# SPI_MUX.net
KiCad netlist of a schematic drawn in EAGLE
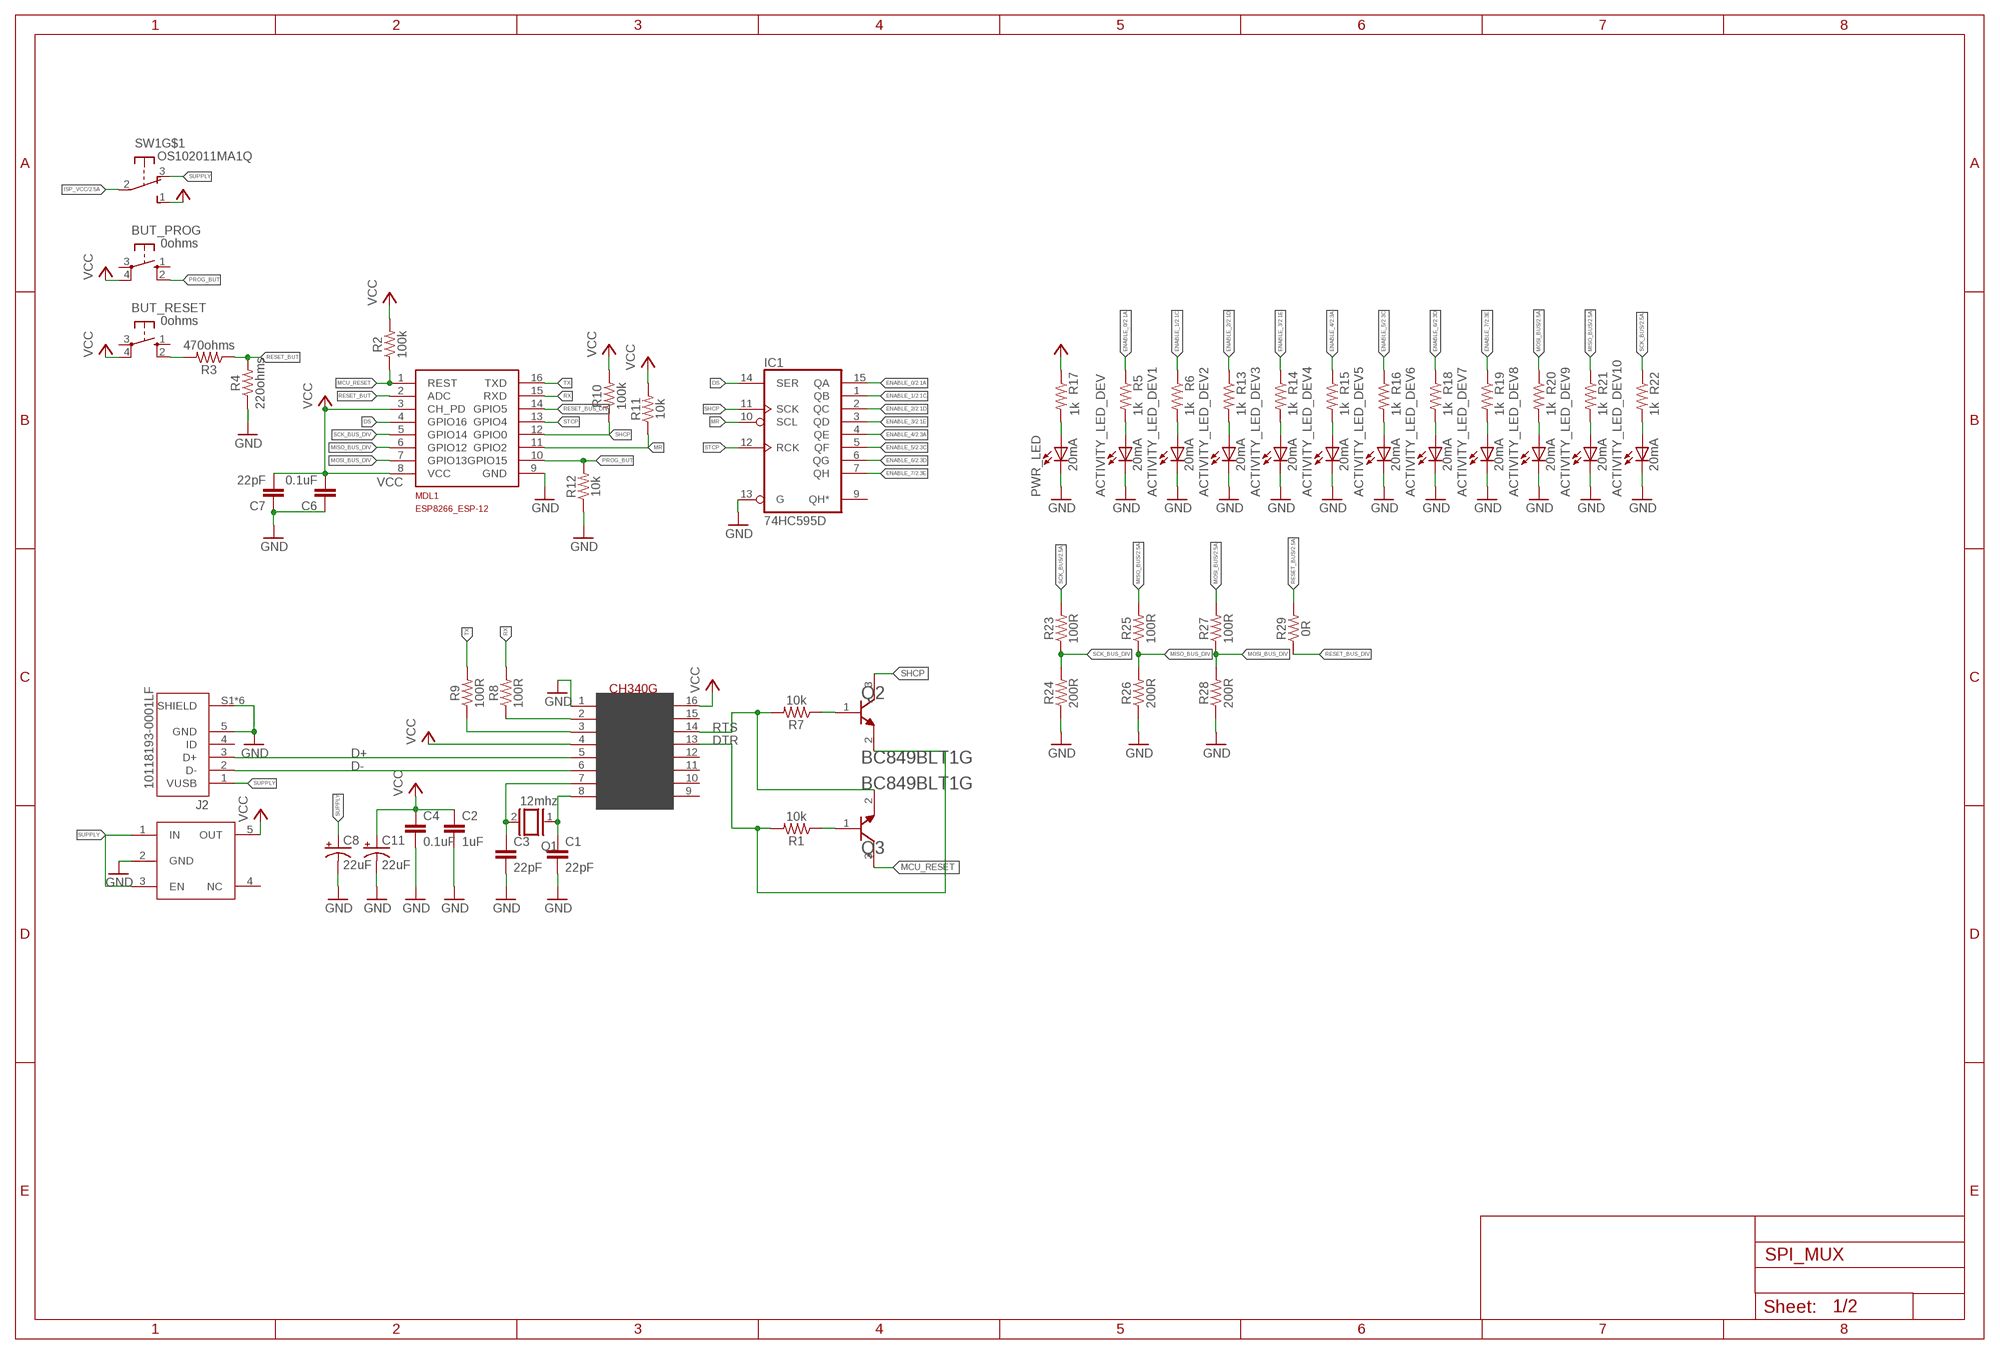
[diagram p0: schematic, sheet 1]
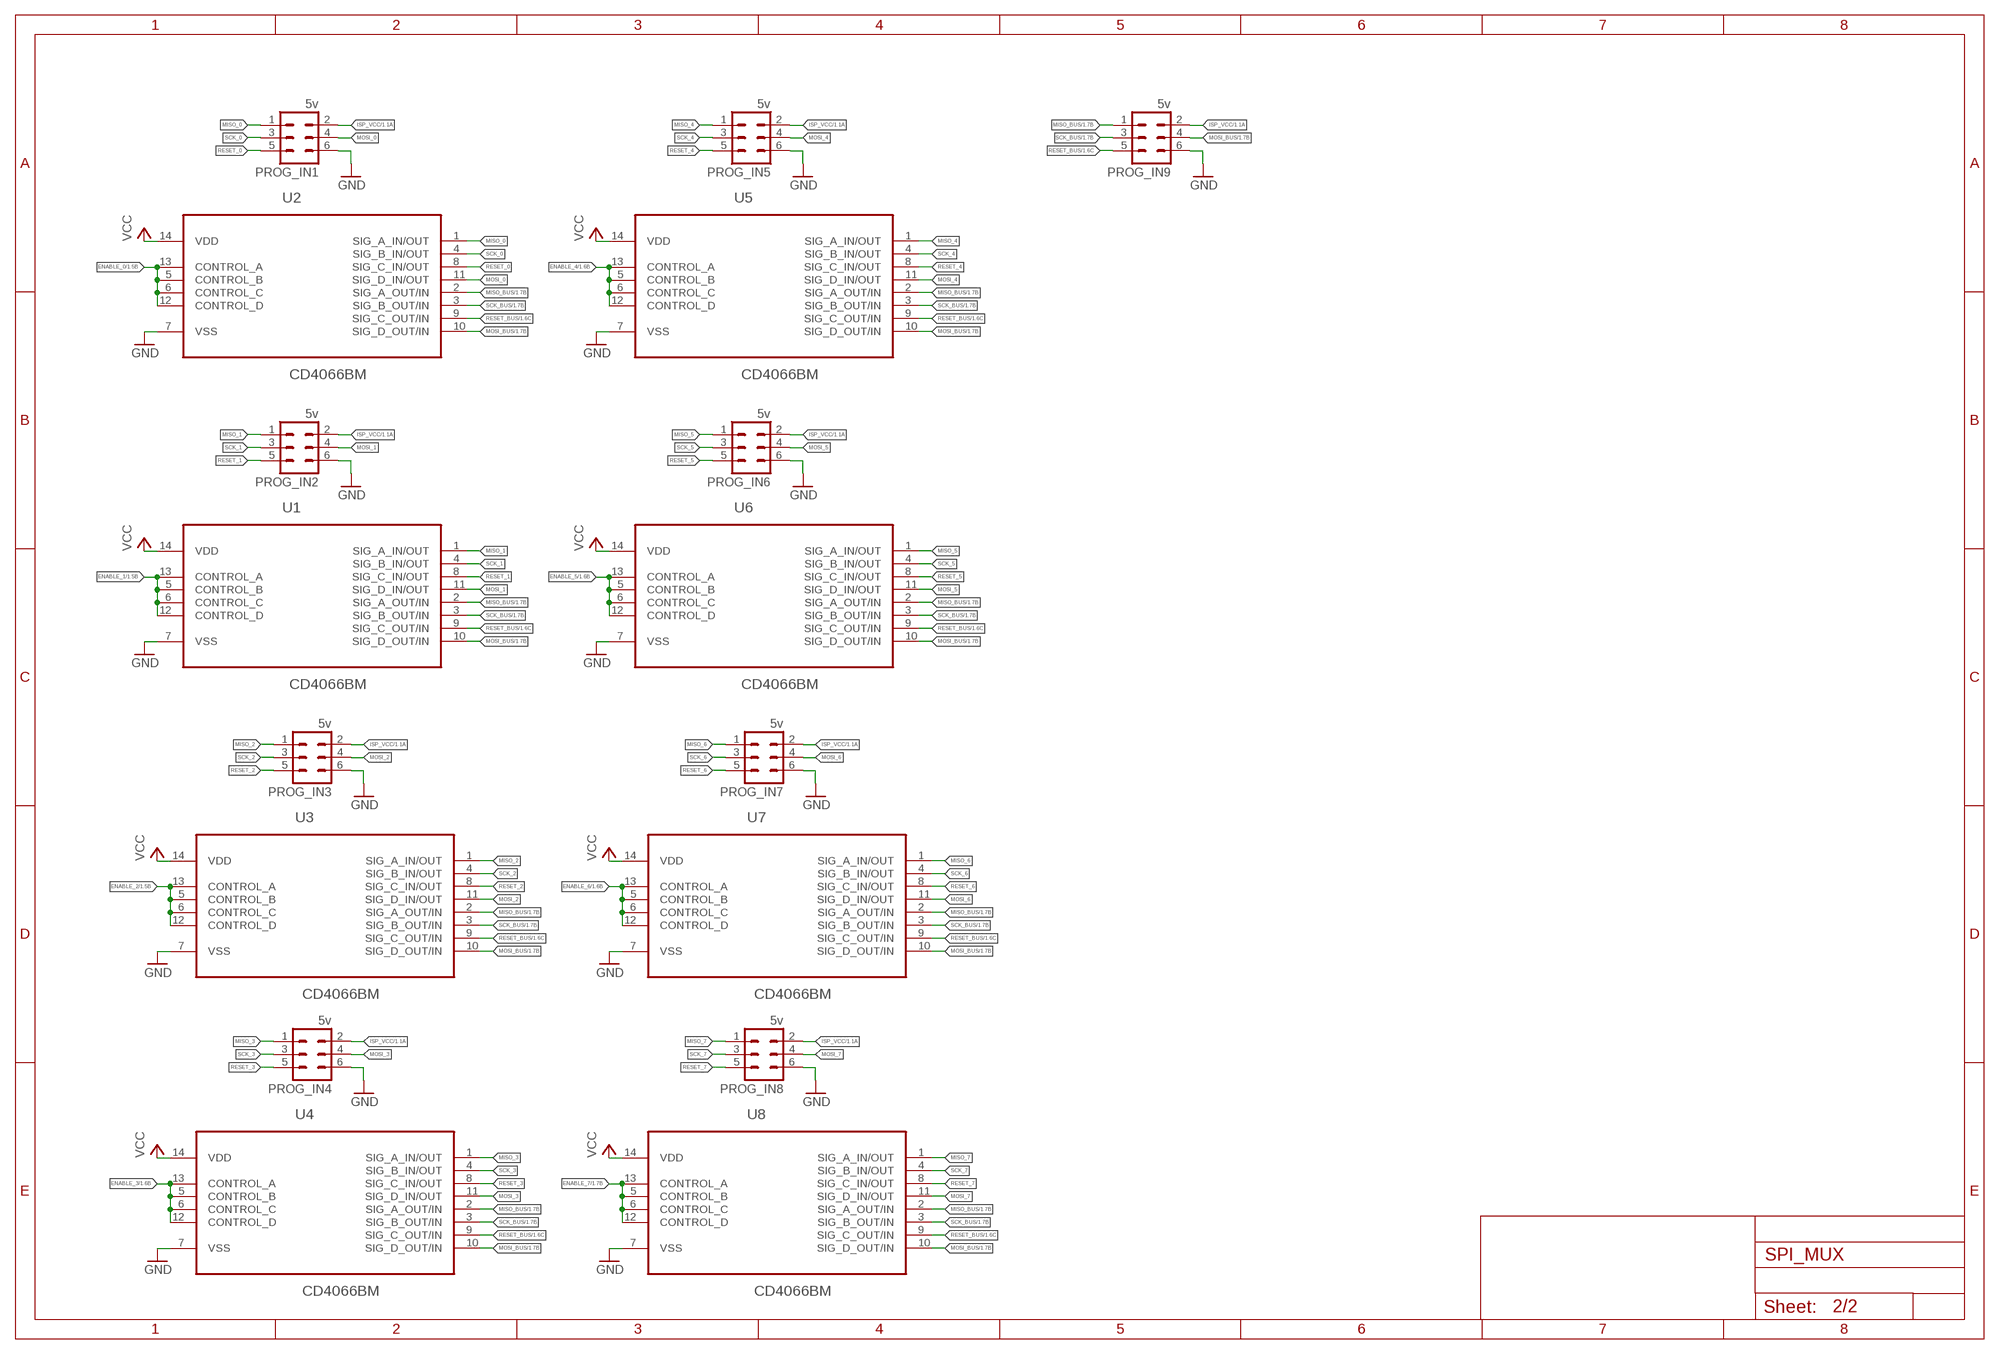
[diagram p1: schematic, sheet 2]

(export (version "E")
  (design (tool "Eeschema 10.0.6"))
  (components
    (comp (ref "3V3_REGULATOR")
      (value "3v3 LDO")
      (footprint "eagle-import:NCP718BSN330T1G")
      (libsource (lib "eagle-import") (part "NCP718BSN330T1G"))
    )
    (comp (ref "ACTIVITY_LED_DEV")
      (value "20mA")
      (footprint "eagle-import:CHIP-LED0603")
      (libsource (lib "eagle-import") (part "LEDCHIP-LED0603"))
    )
    (comp (ref "ACTIVITY_LED_DEV1")
      (value "20mA")
      (footprint "eagle-import:CHIP-LED0603")
      (libsource (lib "eagle-import") (part "LEDCHIP-LED0603"))
    )
    (comp (ref "ACTIVITY_LED_DEV2")
      (value "20mA")
      (footprint "eagle-import:CHIP-LED0603")
      (libsource (lib "eagle-import") (part "LEDCHIP-LED0603"))
    )
    (comp (ref "ACTIVITY_LED_DEV3")
      (value "20mA")
      (footprint "eagle-import:CHIP-LED0603")
      (libsource (lib "eagle-import") (part "LEDCHIP-LED0603"))
    )
    (comp (ref "ACTIVITY_LED_DEV4")
      (value "20mA")
      (footprint "eagle-import:CHIP-LED0603")
      (libsource (lib "eagle-import") (part "LEDCHIP-LED0603"))
    )
    (comp (ref "ACTIVITY_LED_DEV5")
      (value "20mA")
      (footprint "eagle-import:CHIP-LED0603")
      (libsource (lib "eagle-import") (part "LEDCHIP-LED0603"))
    )
    (comp (ref "ACTIVITY_LED_DEV6")
      (value "20mA")
      (footprint "eagle-import:CHIP-LED0603")
      (libsource (lib "eagle-import") (part "LEDCHIP-LED0603"))
    )
    (comp (ref "ACTIVITY_LED_DEV7")
      (value "20mA")
      (footprint "eagle-import:CHIP-LED0603")
      (libsource (lib "eagle-import") (part "LEDCHIP-LED0603"))
    )
    (comp (ref "ACTIVITY_LED_DEV8")
      (value "20mA")
      (footprint "eagle-import:CHIP-LED0603")
      (libsource (lib "eagle-import") (part "LEDCHIP-LED0603"))
    )
    (comp (ref "ACTIVITY_LED_DEV9")
      (value "20mA")
      (footprint "eagle-import:CHIP-LED0603")
      (libsource (lib "eagle-import") (part "LEDCHIP-LED0603"))
    )
    (comp (ref "ACTIVITY_LED_DEV10")
      (value "20mA")
      (footprint "eagle-import:CHIP-LED0603")
      (libsource (lib "eagle-import") (part "LEDCHIP-LED0603"))
    )
    (comp (ref "BUT_PROG")
      (value "0ohms")
      (footprint "eagle-import:B3F-10XX")
      (fields (field (name "MPN") "B3F-1000"))
      (libsource (lib "eagle-import") (part "10-XX"))
    )
    (comp (ref "BUT_RESET")
      (value "0ohms")
      (footprint "eagle-import:B3F-10XX")
      (fields (field (name "MPN") "B3F-1000"))
      (libsource (lib "eagle-import") (part "10-XX"))
    )
    (comp (ref "C1")
      (value "22pF")
      (footprint "eagle-import:C0603")
      (libsource (lib "eagle-import") (part "C-EUC0603"))
    )
    (comp (ref "C2")
      (value "1uF")
      (footprint "eagle-import:C0603")
      (libsource (lib "eagle-import") (part "C-EUC0603"))
    )
    (comp (ref "C3")
      (value "22pF")
      (footprint "eagle-import:C0603")
      (libsource (lib "eagle-import") (part "C-EUC0603"))
    )
    (comp (ref "C4")
      (value "0.1uF")
      (footprint "eagle-import:C0603")
      (libsource (lib "eagle-import") (part "C-EUC0603"))
    )
    (comp (ref "C6")
      (value "0.1uF")
      (footprint "eagle-import:C0603")
      (libsource (lib "eagle-import") (part "C-EUC0603"))
    )
    (comp (ref "C7")
      (value "22pF")
      (footprint "eagle-import:C0603")
      (libsource (lib "eagle-import") (part "C-EUC0603"))
    )
    (comp (ref "C8")
      (value "22uF")
      (footprint "eagle-import:PANASONIC_C")
      (libsource (lib "eagle-import") (part "22UF-POLAR-PANASONIC_C-35V-20%"))
    )
    (comp (ref "C11")
      (value "22uF")
      (footprint "eagle-import:PANASONIC_C")
      (libsource (lib "eagle-import") (part "22UF-POLAR-PANASONIC_C-35V-20%"))
    )
    (comp (ref "IC1")
      (value "74HC595D")
      (footprint "eagle-import:SO16")
      (libsource (lib "eagle-import") (part "74595DHC"))
    )
    (comp (ref "J2")
      (value "10118193-0001LF")
      (footprint "eagle-import:FCI_10118193-0001LF")
      (fields (field (name "MF") "Amphenol FCI"))
      (libsource (lib "eagle-import") (part "10118193-0001LF"))
    )
    (comp (ref "MDL1")
      (value "MCU")
      (footprint "eagle-import:ESP8266-ESP12")
      (libsource (lib "eagle-import") (part "ESP8266-12GPIO04/05_CORRECTED"))
    )
    (comp (ref "PWR_LED")
      (value "20mA")
      (footprint "eagle-import:CHIP-LED0603")
      (libsource (lib "eagle-import") (part "LEDCHIP-LED0603"))
    )
    (comp (ref "Q1")
      (value "12mhz")
      (footprint "eagle-import:QS")
      (libsource (lib "eagle-import") (part "XTAL/S"))
    )
    (comp (ref "Q2")
      (value "ON_SEMICONDUCTOR_BC849BLT1GON_SEMICONDUCTOR_BC849BLT1G_0_0")
      (footprint "eagle-import:ON_SEMICONDUCTOR_BC849BLT1G_0")
      (fields (field (name "MF") "On Semiconductor") (field (name "MPN") "BC849BLT1G"))
      (libsource (lib "eagle-import") (part "ON_SEMICONDUCTOR_BC849BLT1GON_SEMICONDUCTOR_BC849BLT1G_0_0"))
    )
    (comp (ref "Q3")
      (value "ON_SEMICONDUCTOR_BC849BLT1GON_SEMICONDUCTOR_BC849BLT1G_0_0")
      (footprint "eagle-import:ON_SEMICONDUCTOR_BC849BLT1G_0")
      (fields (field (name "MF") "On Semiconductor") (field (name "MPN") "BC849BLT1G"))
      (libsource (lib "eagle-import") (part "ON_SEMICONDUCTOR_BC849BLT1GON_SEMICONDUCTOR_BC849BLT1G_0_0"))
    )
    (comp (ref "R1")
      (value "10k")
      (footprint "eagle-import:0603")
      (libsource (lib "eagle-import") (part "10KOHM-0603-1/10W-1%"))
    )
    (comp (ref "R2")
      (value "100k")
      (footprint "eagle-import:0603")
      (libsource (lib "eagle-import") (part "10KOHM-0603-1/10W-1%"))
    )
    (comp (ref "R3")
      (value "470ohms")
      (footprint "eagle-import:0603")
      (libsource (lib "eagle-import") (part "10KOHM-0603-1/10W-1%"))
    )
    (comp (ref "R4")
      (value "220ohms")
      (footprint "eagle-import:0603")
      (libsource (lib "eagle-import") (part "10KOHM-0603-1/10W-1%"))
    )
    (comp (ref "R5")
      (value "1k")
      (footprint "eagle-import:0603")
      (libsource (lib "eagle-import") (part "10KOHM-0603-1/10W-1%"))
    )
    (comp (ref "R6")
      (value "1k")
      (footprint "eagle-import:0603")
      (libsource (lib "eagle-import") (part "10KOHM-0603-1/10W-1%"))
    )
    (comp (ref "R7")
      (value "10k")
      (footprint "eagle-import:0603")
      (libsource (lib "eagle-import") (part "10KOHM-0603-1/10W-1%"))
    )
    (comp (ref "R8")
      (value "100R")
      (footprint "eagle-import:0603")
      (libsource (lib "eagle-import") (part "10KOHM-0603-1/10W-1%"))
    )
    (comp (ref "R9")
      (value "100R")
      (footprint "eagle-import:0603")
      (libsource (lib "eagle-import") (part "10KOHM-0603-1/10W-1%"))
    )
    (comp (ref "R10")
      (value "100k")
      (footprint "eagle-import:0603")
      (libsource (lib "eagle-import") (part "10KOHM-0603-1/10W-1%"))
    )
    (comp (ref "R11")
      (value "10k")
      (footprint "eagle-import:0603")
      (libsource (lib "eagle-import") (part "10KOHM-0603-1/10W-1%"))
    )
    (comp (ref "R12")
      (value "10k")
      (footprint "eagle-import:0603")
      (libsource (lib "eagle-import") (part "10KOHM-0603-1/10W-1%"))
    )
    (comp (ref "R13")
      (value "1k")
      (footprint "eagle-import:0603")
      (libsource (lib "eagle-import") (part "10KOHM-0603-1/10W-1%"))
    )
    (comp (ref "R14")
      (value "1k")
      (footprint "eagle-import:0603")
      (libsource (lib "eagle-import") (part "10KOHM-0603-1/10W-1%"))
    )
    (comp (ref "R15")
      (value "1k")
      (footprint "eagle-import:0603")
      (libsource (lib "eagle-import") (part "10KOHM-0603-1/10W-1%"))
    )
    (comp (ref "R16")
      (value "1k")
      (footprint "eagle-import:0603")
      (libsource (lib "eagle-import") (part "10KOHM-0603-1/10W-1%"))
    )
    (comp (ref "R17")
      (value "1k")
      (footprint "eagle-import:0603")
      (libsource (lib "eagle-import") (part "10KOHM-0603-1/10W-1%"))
    )
    (comp (ref "R18")
      (value "1k")
      (footprint "eagle-import:0603")
      (libsource (lib "eagle-import") (part "10KOHM-0603-1/10W-1%"))
    )
    (comp (ref "R19")
      (value "1k")
      (footprint "eagle-import:0603")
      (libsource (lib "eagle-import") (part "10KOHM-0603-1/10W-1%"))
    )
    (comp (ref "R20")
      (value "1k")
      (footprint "eagle-import:0603")
      (libsource (lib "eagle-import") (part "10KOHM-0603-1/10W-1%"))
    )
    (comp (ref "R21")
      (value "1k")
      (footprint "eagle-import:0603")
      (libsource (lib "eagle-import") (part "10KOHM-0603-1/10W-1%"))
    )
    (comp (ref "R22")
      (value "1k")
      (footprint "eagle-import:0603")
      (libsource (lib "eagle-import") (part "10KOHM-0603-1/10W-1%"))
    )
    (comp (ref "R23")
      (value "100R")
      (footprint "eagle-import:0603")
      (libsource (lib "eagle-import") (part "10KOHM-0603-1/10W-1%"))
    )
    (comp (ref "R24")
      (value "200R")
      (footprint "eagle-import:0603")
      (libsource (lib "eagle-import") (part "10KOHM-0603-1/10W-1%"))
    )
    (comp (ref "R25")
      (value "100R")
      (footprint "eagle-import:0603")
      (libsource (lib "eagle-import") (part "10KOHM-0603-1/10W-1%"))
    )
    (comp (ref "R26")
      (value "200R")
      (footprint "eagle-import:0603")
      (libsource (lib "eagle-import") (part "10KOHM-0603-1/10W-1%"))
    )
    (comp (ref "R27")
      (value "100R")
      (footprint "eagle-import:0603")
      (libsource (lib "eagle-import") (part "10KOHM-0603-1/10W-1%"))
    )
    (comp (ref "R28")
      (value "200R")
      (footprint "eagle-import:0603")
      (libsource (lib "eagle-import") (part "10KOHM-0603-1/10W-1%"))
    )
    (comp (ref "R29")
      (value "0R")
      (footprint "eagle-import:0603")
      (libsource (lib "eagle-import") (part "10KOHM-0603-1/10W-1%"))
    )
    (comp (ref "SW1")
      (value "OS102011MA1Q")
      (footprint "eagle-import:OS102011MA1Q")
      (libsource (lib "eagle-import") (part "OS102011MA1Q"))
    )
    (comp (ref "U$1")
      (value "CH340G")
      (footprint "eagle-import:SOIC16")
      (libsource (lib "eagle-import") (part "CH340G"))
    )
    (comp (ref "PROG_IN1")
      (value "5v")
      (footprint "eagle-import:MA03-2")
      (libsource (lib "eagle-import") (part "MA03-2"))
    )
    (comp (ref "PROG_IN2")
      (value "5v")
      (footprint "eagle-import:MA03-2")
      (libsource (lib "eagle-import") (part "MA03-2"))
    )
    (comp (ref "PROG_IN3")
      (value "5v")
      (footprint "eagle-import:MA03-2")
      (libsource (lib "eagle-import") (part "MA03-2"))
    )
    (comp (ref "PROG_IN4")
      (value "5v")
      (footprint "eagle-import:MA03-2")
      (libsource (lib "eagle-import") (part "MA03-2"))
    )
    (comp (ref "PROG_IN5")
      (value "5v")
      (footprint "eagle-import:MA03-2")
      (libsource (lib "eagle-import") (part "MA03-2"))
    )
    (comp (ref "PROG_IN6")
      (value "5v")
      (footprint "eagle-import:MA03-2")
      (libsource (lib "eagle-import") (part "MA03-2"))
    )
    (comp (ref "PROG_IN7")
      (value "5v")
      (footprint "eagle-import:MA03-2")
      (libsource (lib "eagle-import") (part "MA03-2"))
    )
    (comp (ref "PROG_IN8")
      (value "5v")
      (footprint "eagle-import:MA03-2")
      (libsource (lib "eagle-import") (part "MA03-2"))
    )
    (comp (ref "PROG_IN9")
      (value "5v")
      (footprint "eagle-import:MA03-2")
      (libsource (lib "eagle-import") (part "MA03-2"))
    )
    (comp (ref "U1")
      (value "CD4066BM")
      (footprint "eagle-import:SOIC127P600X175-14N")
      (libsource (lib "eagle-import") (part "CD4066BM"))
    )
    (comp (ref "U2")
      (value "CD4066BM")
      (footprint "eagle-import:SOIC127P600X175-14N")
      (libsource (lib "eagle-import") (part "CD4066BM"))
    )
    (comp (ref "U3")
      (value "CD4066BM")
      (footprint "eagle-import:SOIC127P600X175-14N")
      (libsource (lib "eagle-import") (part "CD4066BM"))
    )
    (comp (ref "U4")
      (value "CD4066BM")
      (footprint "eagle-import:SOIC127P600X175-14N")
      (libsource (lib "eagle-import") (part "CD4066BM"))
    )
    (comp (ref "U5")
      (value "CD4066BM")
      (footprint "eagle-import:SOIC127P600X175-14N")
      (libsource (lib "eagle-import") (part "CD4066BM"))
    )
    (comp (ref "U6")
      (value "CD4066BM")
      (footprint "eagle-import:SOIC127P600X175-14N")
      (libsource (lib "eagle-import") (part "CD4066BM"))
    )
    (comp (ref "U7")
      (value "CD4066BM")
      (footprint "eagle-import:SOIC127P600X175-14N")
      (libsource (lib "eagle-import") (part "CD4066BM"))
    )
    (comp (ref "U8")
      (value "CD4066BM")
      (footprint "eagle-import:SOIC127P600X175-14N")
      (libsource (lib "eagle-import") (part "CD4066BM"))
    )
  )
  (nets
    (net (code "1") (name "D+") (class "Default")
      (node (ref "J2") (pin "3") (pinfunction "D+_3") (pintype "passive"))
      (node (ref "U$1") (pin "5") (pinfunction "D+_5") (pintype "bidirectional"))
    )
    (net (code "2") (name "D-") (class "Default")
      (node (ref "J2") (pin "2") (pinfunction "D-_2") (pintype "passive"))
      (node (ref "U$1") (pin "6") (pinfunction "D-_6") (pintype "bidirectional"))
    )
    (net (code "3") (name "DS") (class "Default")
      (node (ref "IC1") (pin "14") (pinfunction "SER_14") (pintype "input"))
      (node (ref "MDL1") (pin "4") (pinfunction "GPIO16_4") (pintype "bidirectional"))
    )
    (net (code "4") (name "DTR") (class "Default")
      (node (ref "Q2") (pin "2") (pinfunction "E_2") (pintype "passive"))
      (node (ref "R1") (pin "2") (pinfunction "2_2") (pintype "passive"))
      (node (ref "U$1") (pin "13") (pinfunction "DTR_13") (pintype "bidirectional"))
    )
    (net (code "5") (name "ENABLE_0") (class "Default")
      (node (ref "IC1") (pin "15") (pinfunction "QA_15") (pintype "tri_state"))
      (node (ref "R5") (pin "1") (pinfunction "1_1") (pintype "passive"))
      (node (ref "U2") (pin "12") (pinfunction "CONTROL_D_12") (pintype "input"))
      (node (ref "U2") (pin "13") (pinfunction "CONTROL_A_13") (pintype "input"))
      (node (ref "U2") (pin "5") (pinfunction "CONTROL_B_5") (pintype "input"))
      (node (ref "U2") (pin "6") (pinfunction "CONTROL_C_6") (pintype "input"))
    )
    (net (code "6") (name "ENABLE_1") (class "Default")
      (node (ref "IC1") (pin "1") (pinfunction "QB_1") (pintype "tri_state"))
      (node (ref "R6") (pin "1") (pinfunction "1_1") (pintype "passive"))
      (node (ref "U1") (pin "12") (pinfunction "CONTROL_D_12") (pintype "input"))
      (node (ref "U1") (pin "13") (pinfunction "CONTROL_A_13") (pintype "input"))
      (node (ref "U1") (pin "5") (pinfunction "CONTROL_B_5") (pintype "input"))
      (node (ref "U1") (pin "6") (pinfunction "CONTROL_C_6") (pintype "input"))
    )
    (net (code "7") (name "ENABLE_2") (class "Default")
      (node (ref "IC1") (pin "2") (pinfunction "QC_2") (pintype "tri_state"))
      (node (ref "R13") (pin "1") (pinfunction "1_1") (pintype "passive"))
      (node (ref "U3") (pin "12") (pinfunction "CONTROL_D_12") (pintype "input"))
      (node (ref "U3") (pin "13") (pinfunction "CONTROL_A_13") (pintype "input"))
      (node (ref "U3") (pin "5") (pinfunction "CONTROL_B_5") (pintype "input"))
      (node (ref "U3") (pin "6") (pinfunction "CONTROL_C_6") (pintype "input"))
    )
    (net (code "8") (name "ENABLE_3") (class "Default")
      (node (ref "IC1") (pin "3") (pinfunction "QD_3") (pintype "tri_state"))
      (node (ref "R14") (pin "1") (pinfunction "1_1") (pintype "passive"))
      (node (ref "U4") (pin "12") (pinfunction "CONTROL_D_12") (pintype "input"))
      (node (ref "U4") (pin "13") (pinfunction "CONTROL_A_13") (pintype "input"))
      (node (ref "U4") (pin "5") (pinfunction "CONTROL_B_5") (pintype "input"))
      (node (ref "U4") (pin "6") (pinfunction "CONTROL_C_6") (pintype "input"))
    )
    (net (code "9") (name "ENABLE_4") (class "Default")
      (node (ref "IC1") (pin "4") (pinfunction "QE_4") (pintype "tri_state"))
      (node (ref "R15") (pin "1") (pinfunction "1_1") (pintype "passive"))
      (node (ref "U5") (pin "12") (pinfunction "CONTROL_D_12") (pintype "input"))
      (node (ref "U5") (pin "13") (pinfunction "CONTROL_A_13") (pintype "input"))
      (node (ref "U5") (pin "5") (pinfunction "CONTROL_B_5") (pintype "input"))
      (node (ref "U5") (pin "6") (pinfunction "CONTROL_C_6") (pintype "input"))
    )
    (net (code "10") (name "ENABLE_5") (class "Default")
      (node (ref "IC1") (pin "5") (pinfunction "QF_5") (pintype "tri_state"))
      (node (ref "R16") (pin "1") (pinfunction "1_1") (pintype "passive"))
      (node (ref "U6") (pin "12") (pinfunction "CONTROL_D_12") (pintype "input"))
      (node (ref "U6") (pin "13") (pinfunction "CONTROL_A_13") (pintype "input"))
      (node (ref "U6") (pin "5") (pinfunction "CONTROL_B_5") (pintype "input"))
      (node (ref "U6") (pin "6") (pinfunction "CONTROL_C_6") (pintype "input"))
    )
    (net (code "11") (name "ENABLE_6") (class "Default")
      (node (ref "IC1") (pin "6") (pinfunction "QG_6") (pintype "tri_state"))
      (node (ref "R18") (pin "1") (pinfunction "1_1") (pintype "passive"))
      (node (ref "U7") (pin "12") (pinfunction "CONTROL_D_12") (pintype "input"))
      (node (ref "U7") (pin "13") (pinfunction "CONTROL_A_13") (pintype "input"))
      (node (ref "U7") (pin "5") (pinfunction "CONTROL_B_5") (pintype "input"))
      (node (ref "U7") (pin "6") (pinfunction "CONTROL_C_6") (pintype "input"))
    )
    (net (code "12") (name "ENABLE_7") (class "Default")
      (node (ref "IC1") (pin "7") (pinfunction "QH_7") (pintype "tri_state"))
      (node (ref "R19") (pin "1") (pinfunction "1_1") (pintype "passive"))
      (node (ref "U8") (pin "12") (pinfunction "CONTROL_D_12") (pintype "input"))
      (node (ref "U8") (pin "13") (pinfunction "CONTROL_A_13") (pintype "input"))
      (node (ref "U8") (pin "5") (pinfunction "CONTROL_B_5") (pintype "input"))
      (node (ref "U8") (pin "6") (pinfunction "CONTROL_C_6") (pintype "input"))
    )
    (net (code "13") (name "GND") (class "Default")
      (node (ref "3V3_REGULATOR") (pin "2") (pinfunction "GND_2") (pintype "power_in"))
      (node (ref "ACTIVITY_LED_DEV") (pin "C") (pinfunction "C_C") (pintype "passive"))
      (node (ref "ACTIVITY_LED_DEV1") (pin "C") (pinfunction "C_C") (pintype "passive"))
      (node (ref "ACTIVITY_LED_DEV10") (pin "C") (pinfunction "C_C") (pintype "passive"))
      (node (ref "ACTIVITY_LED_DEV2") (pin "C") (pinfunction "C_C") (pintype "passive"))
      (node (ref "ACTIVITY_LED_DEV3") (pin "C") (pinfunction "C_C") (pintype "passive"))
      (node (ref "ACTIVITY_LED_DEV4") (pin "C") (pinfunction "C_C") (pintype "passive"))
      (node (ref "ACTIVITY_LED_DEV5") (pin "C") (pinfunction "C_C") (pintype "passive"))
      (node (ref "ACTIVITY_LED_DEV6") (pin "C") (pinfunction "C_C") (pintype "passive"))
      (node (ref "ACTIVITY_LED_DEV7") (pin "C") (pinfunction "C_C") (pintype "passive"))
      (node (ref "ACTIVITY_LED_DEV8") (pin "C") (pinfunction "C_C") (pintype "passive"))
      (node (ref "ACTIVITY_LED_DEV9") (pin "C") (pinfunction "C_C") (pintype "passive"))
      (node (ref "C1") (pin "2") (pinfunction "2_2") (pintype "passive"))
      (node (ref "C11") (pin "-") (pinfunction "-_-") (pintype "passive"))
      (node (ref "C2") (pin "2") (pinfunction "2_2") (pintype "passive"))
      (node (ref "C3") (pin "2") (pinfunction "2_2") (pintype "passive"))
      (node (ref "C4") (pin "2") (pinfunction "2_2") (pintype "passive"))
      (node (ref "C6") (pin "1") (pinfunction "1_1") (pintype "passive"))
      (node (ref "C7") (pin "1") (pinfunction "1_1") (pintype "passive"))
      (node (ref "C8") (pin "-") (pinfunction "-_-") (pintype "passive"))
      (node (ref "IC1") (pin "13") (pinfunction "G_13") (pintype "input"))
      (node (ref "J2") (pin "5") (pinfunction "GND_5") (pintype "passive"))
      (node (ref "J2") (pin "S1") (pinfunction "SHIELD_S1") (pintype "passive"))
      (node (ref "J2") (pin "S2") (pinfunction "SHIELD_S2") (pintype "passive"))
      (node (ref "J2") (pin "S3") (pinfunction "SHIELD_S3") (pintype "passive"))
      (node (ref "J2") (pin "S4") (pinfunction "SHIELD_S4") (pintype "passive"))
      (node (ref "J2") (pin "S5") (pinfunction "SHIELD_S5") (pintype "passive"))
      (node (ref "J2") (pin "S6") (pinfunction "SHIELD_S6") (pintype "passive"))
      (node (ref "MDL1") (pin "9") (pinfunction "GND_9") (pintype "bidirectional"))
      (node (ref "PROG_IN1") (pin "6") (pinfunction "6_6") (pintype "passive"))
      (node (ref "PROG_IN2") (pin "6") (pinfunction "6_6") (pintype "passive"))
      (node (ref "PROG_IN3") (pin "6") (pinfunction "6_6") (pintype "passive"))
      (node (ref "PROG_IN4") (pin "6") (pinfunction "6_6") (pintype "passive"))
      (node (ref "PROG_IN5") (pin "6") (pinfunction "6_6") (pintype "passive"))
      (node (ref "PROG_IN6") (pin "6") (pinfunction "6_6") (pintype "passive"))
      (node (ref "PROG_IN7") (pin "6") (pinfunction "6_6") (pintype "passive"))
      (node (ref "PROG_IN8") (pin "6") (pinfunction "6_6") (pintype "passive"))
      (node (ref "PROG_IN9") (pin "6") (pinfunction "6_6") (pintype "passive"))
      (node (ref "PWR_LED") (pin "C") (pinfunction "C_C") (pintype "passive"))
      (node (ref "R12") (pin "1") (pinfunction "1_1") (pintype "passive"))
      (node (ref "R24") (pin "1") (pinfunction "1_1") (pintype "passive"))
      (node (ref "R26") (pin "1") (pinfunction "1_1") (pintype "passive"))
      (node (ref "R28") (pin "1") (pinfunction "1_1") (pintype "passive"))
      (node (ref "R4") (pin "1") (pinfunction "1_1") (pintype "passive"))
      (node (ref "U$1") (pin "1") (pinfunction "GND_1") (pintype "bidirectional"))
      (node (ref "U1") (pin "7") (pinfunction "VSS_7") (pintype "power_in"))
      (node (ref "U2") (pin "7") (pinfunction "VSS_7") (pintype "power_in"))
      (node (ref "U3") (pin "7") (pinfunction "VSS_7") (pintype "power_in"))
      (node (ref "U4") (pin "7") (pinfunction "VSS_7") (pintype "power_in"))
      (node (ref "U5") (pin "7") (pinfunction "VSS_7") (pintype "power_in"))
      (node (ref "U6") (pin "7") (pinfunction "VSS_7") (pintype "power_in"))
      (node (ref "U7") (pin "7") (pinfunction "VSS_7") (pintype "power_in"))
      (node (ref "U8") (pin "7") (pinfunction "VSS_7") (pintype "power_in"))
    )
    (net (code "14") (name "ISP_VCC") (class "Default")
      (node (ref "PROG_IN1") (pin "2") (pinfunction "2_2") (pintype "passive"))
      (node (ref "PROG_IN2") (pin "2") (pinfunction "2_2") (pintype "passive"))
      (node (ref "PROG_IN3") (pin "2") (pinfunction "2_2") (pintype "passive"))
      (node (ref "PROG_IN4") (pin "2") (pinfunction "2_2") (pintype "passive"))
      (node (ref "PROG_IN5") (pin "2") (pinfunction "2_2") (pintype "passive"))
      (node (ref "PROG_IN6") (pin "2") (pinfunction "2_2") (pintype "passive"))
      (node (ref "PROG_IN7") (pin "2") (pinfunction "2_2") (pintype "passive"))
      (node (ref "PROG_IN8") (pin "2") (pinfunction "2_2") (pintype "passive"))
      (node (ref "PROG_IN9") (pin "2") (pinfunction "2_2") (pintype "passive"))
      (node (ref "SW1") (pin "2") (pinfunction "P_2") (pintype "passive"))
    )
    (net (code "15") (name "MCU_RESET") (class "Default")
      (node (ref "MDL1") (pin "1") (pinfunction "REST_1") (pintype "bidirectional"))
      (node (ref "Q3") (pin "3") (pinfunction "C_3") (pintype "passive"))
      (node (ref "R2") (pin "1") (pinfunction "1_1") (pintype "passive"))
    )
    (net (code "16") (name "MISO_0") (class "Default")
      (node (ref "PROG_IN1") (pin "1") (pinfunction "1_1") (pintype "passive"))
      (node (ref "U2") (pin "1") (pinfunction "SIG_A_IN/OUT_1") (pintype "bidirectional"))
    )
    (net (code "17") (name "MISO_1") (class "Default")
      (node (ref "PROG_IN2") (pin "1") (pinfunction "1_1") (pintype "passive"))
      (node (ref "U1") (pin "1") (pinfunction "SIG_A_IN/OUT_1") (pintype "bidirectional"))
    )
    (net (code "18") (name "MISO_2") (class "Default")
      (node (ref "PROG_IN3") (pin "1") (pinfunction "1_1") (pintype "passive"))
      (node (ref "U3") (pin "1") (pinfunction "SIG_A_IN/OUT_1") (pintype "bidirectional"))
    )
    (net (code "19") (name "MISO_3") (class "Default")
      (node (ref "PROG_IN4") (pin "1") (pinfunction "1_1") (pintype "passive"))
      (node (ref "U4") (pin "1") (pinfunction "SIG_A_IN/OUT_1") (pintype "bidirectional"))
    )
    (net (code "20") (name "MISO_4") (class "Default")
      (node (ref "PROG_IN5") (pin "1") (pinfunction "1_1") (pintype "passive"))
      (node (ref "U5") (pin "1") (pinfunction "SIG_A_IN/OUT_1") (pintype "bidirectional"))
    )
    (net (code "21") (name "MISO_5") (class "Default")
      (node (ref "PROG_IN6") (pin "1") (pinfunction "1_1") (pintype "passive"))
      (node (ref "U6") (pin "1") (pinfunction "SIG_A_IN/OUT_1") (pintype "bidirectional"))
    )
    (net (code "22") (name "MISO_6") (class "Default")
      (node (ref "PROG_IN7") (pin "1") (pinfunction "1_1") (pintype "passive"))
      (node (ref "U7") (pin "1") (pinfunction "SIG_A_IN/OUT_1") (pintype "bidirectional"))
    )
    (net (code "23") (name "MISO_7") (class "Default")
      (node (ref "PROG_IN8") (pin "1") (pinfunction "1_1") (pintype "passive"))
      (node (ref "U8") (pin "1") (pinfunction "SIG_A_IN/OUT_1") (pintype "bidirectional"))
    )
    (net (code "24") (name "MISO_BUS") (class "Default")
      (node (ref "PROG_IN9") (pin "1") (pinfunction "1_1") (pintype "passive"))
      (node (ref "R21") (pin "1") (pinfunction "1_1") (pintype "passive"))
      (node (ref "R25") (pin "2") (pinfunction "2_2") (pintype "passive"))
      (node (ref "U1") (pin "2") (pinfunction "SIG_A_OUT/IN_2") (pintype "bidirectional"))
      (node (ref "U2") (pin "2") (pinfunction "SIG_A_OUT/IN_2") (pintype "bidirectional"))
      (node (ref "U3") (pin "2") (pinfunction "SIG_A_OUT/IN_2") (pintype "bidirectional"))
      (node (ref "U4") (pin "2") (pinfunction "SIG_A_OUT/IN_2") (pintype "bidirectional"))
      (node (ref "U5") (pin "2") (pinfunction "SIG_A_OUT/IN_2") (pintype "bidirectional"))
      (node (ref "U6") (pin "2") (pinfunction "SIG_A_OUT/IN_2") (pintype "bidirectional"))
      (node (ref "U7") (pin "2") (pinfunction "SIG_A_OUT/IN_2") (pintype "bidirectional"))
      (node (ref "U8") (pin "2") (pinfunction "SIG_A_OUT/IN_2") (pintype "bidirectional"))
    )
    (net (code "25") (name "MISO_BUS_DIV") (class "Default")
      (node (ref "MDL1") (pin "6") (pinfunction "GPIO12_6") (pintype "bidirectional"))
      (node (ref "R25") (pin "1") (pinfunction "1_1") (pintype "passive"))
      (node (ref "R26") (pin "2") (pinfunction "2_2") (pintype "passive"))
    )
    (net (code "26") (name "MOSI_0") (class "Default")
      (node (ref "PROG_IN1") (pin "4") (pinfunction "4_4") (pintype "passive"))
      (node (ref "U2") (pin "11") (pinfunction "SIG_D_IN/OUT_11") (pintype "bidirectional"))
    )
    (net (code "27") (name "MOSI_1") (class "Default")
      (node (ref "PROG_IN2") (pin "4") (pinfunction "4_4") (pintype "passive"))
      (node (ref "U1") (pin "11") (pinfunction "SIG_D_IN/OUT_11") (pintype "bidirectional"))
    )
    (net (code "28") (name "MOSI_2") (class "Default")
      (node (ref "PROG_IN3") (pin "4") (pinfunction "4_4") (pintype "passive"))
      (node (ref "U3") (pin "11") (pinfunction "SIG_D_IN/OUT_11") (pintype "bidirectional"))
    )
    (net (code "29") (name "MOSI_3") (class "Default")
      (node (ref "PROG_IN4") (pin "4") (pinfunction "4_4") (pintype "passive"))
      (node (ref "U4") (pin "11") (pinfunction "SIG_D_IN/OUT_11") (pintype "bidirectional"))
    )
    (net (code "30") (name "MOSI_4") (class "Default")
      (node (ref "PROG_IN5") (pin "4") (pinfunction "4_4") (pintype "passive"))
      (node (ref "U5") (pin "11") (pinfunction "SIG_D_IN/OUT_11") (pintype "bidirectional"))
    )
    (net (code "31") (name "MOSI_5") (class "Default")
      (node (ref "PROG_IN6") (pin "4") (pinfunction "4_4") (pintype "passive"))
      (node (ref "U6") (pin "11") (pinfunction "SIG_D_IN/OUT_11") (pintype "bidirectional"))
    )
    (net (code "32") (name "MOSI_6") (class "Default")
      (node (ref "PROG_IN7") (pin "4") (pinfunction "4_4") (pintype "passive"))
      (node (ref "U7") (pin "11") (pinfunction "SIG_D_IN/OUT_11") (pintype "bidirectional"))
    )
    (net (code "33") (name "MOSI_7") (class "Default")
      (node (ref "PROG_IN8") (pin "4") (pinfunction "4_4") (pintype "passive"))
      (node (ref "U8") (pin "11") (pinfunction "SIG_D_IN/OUT_11") (pintype "bidirectional"))
    )
    (net (code "34") (name "MOSI_BUS") (class "Default")
      (node (ref "PROG_IN9") (pin "4") (pinfunction "4_4") (pintype "passive"))
      (node (ref "R20") (pin "1") (pinfunction "1_1") (pintype "passive"))
      (node (ref "R27") (pin "2") (pinfunction "2_2") (pintype "passive"))
      (node (ref "U1") (pin "10") (pinfunction "SIG_D_OUT/IN_10") (pintype "bidirectional"))
      (node (ref "U2") (pin "10") (pinfunction "SIG_D_OUT/IN_10") (pintype "bidirectional"))
      (node (ref "U3") (pin "10") (pinfunction "SIG_D_OUT/IN_10") (pintype "bidirectional"))
      (node (ref "U4") (pin "10") (pinfunction "SIG_D_OUT/IN_10") (pintype "bidirectional"))
      (node (ref "U5") (pin "10") (pinfunction "SIG_D_OUT/IN_10") (pintype "bidirectional"))
      (node (ref "U6") (pin "10") (pinfunction "SIG_D_OUT/IN_10") (pintype "bidirectional"))
      (node (ref "U7") (pin "10") (pinfunction "SIG_D_OUT/IN_10") (pintype "bidirectional"))
      (node (ref "U8") (pin "10") (pinfunction "SIG_D_OUT/IN_10") (pintype "bidirectional"))
    )
    (net (code "35") (name "MOSI_BUS_DIV") (class "Default")
      (node (ref "MDL1") (pin "7") (pinfunction "GPIO13_7") (pintype "bidirectional"))
      (node (ref "R27") (pin "1") (pinfunction "1_1") (pintype "passive"))
      (node (ref "R28") (pin "2") (pinfunction "2_2") (pintype "passive"))
    )
    (net (code "36") (name "MR") (class "Default")
      (node (ref "IC1") (pin "10") (pinfunction "SCL_10") (pintype "input"))
      (node (ref "MDL1") (pin "11") (pinfunction "GPIO2_11") (pintype "bidirectional"))
      (node (ref "R11") (pin "1") (pinfunction "1_1") (pintype "passive"))
    )
    (net (code "37") (name "Net-(ACTIVITY_LED_DEV-PadA)") (class "Default")
      (node (ref "ACTIVITY_LED_DEV") (pin "A") (pinfunction "A_A") (pintype "passive"))
      (node (ref "R5") (pin "2") (pinfunction "2_2") (pintype "passive"))
    )
    (net (code "38") (name "Net-(ACTIVITY_LED_DEV1-PadA)") (class "Default")
      (node (ref "ACTIVITY_LED_DEV1") (pin "A") (pinfunction "A_A") (pintype "passive"))
      (node (ref "R6") (pin "2") (pinfunction "2_2") (pintype "passive"))
    )
    (net (code "39") (name "Net-(ACTIVITY_LED_DEV2-PadA)") (class "Default")
      (node (ref "ACTIVITY_LED_DEV2") (pin "A") (pinfunction "A_A") (pintype "passive"))
      (node (ref "R13") (pin "2") (pinfunction "2_2") (pintype "passive"))
    )
    (net (code "40") (name "Net-(ACTIVITY_LED_DEV3-PadA)") (class "Default")
      (node (ref "ACTIVITY_LED_DEV3") (pin "A") (pinfunction "A_A") (pintype "passive"))
      (node (ref "R14") (pin "2") (pinfunction "2_2") (pintype "passive"))
    )
    (net (code "41") (name "Net-(ACTIVITY_LED_DEV4-PadA)") (class "Default")
      (node (ref "ACTIVITY_LED_DEV4") (pin "A") (pinfunction "A_A") (pintype "passive"))
      (node (ref "R15") (pin "2") (pinfunction "2_2") (pintype "passive"))
    )
    (net (code "42") (name "Net-(ACTIVITY_LED_DEV5-PadA)") (class "Default")
      (node (ref "ACTIVITY_LED_DEV5") (pin "A") (pinfunction "A_A") (pintype "passive"))
      (node (ref "R16") (pin "2") (pinfunction "2_2") (pintype "passive"))
    )
    (net (code "43") (name "Net-(ACTIVITY_LED_DEV6-PadA)") (class "Default")
      (node (ref "ACTIVITY_LED_DEV6") (pin "A") (pinfunction "A_A") (pintype "passive"))
      (node (ref "R18") (pin "2") (pinfunction "2_2") (pintype "passive"))
    )
    (net (code "44") (name "Net-(ACTIVITY_LED_DEV7-PadA)") (class "Default")
      (node (ref "ACTIVITY_LED_DEV7") (pin "A") (pinfunction "A_A") (pintype "passive"))
      (node (ref "R19") (pin "2") (pinfunction "2_2") (pintype "passive"))
    )
    (net (code "45") (name "Net-(ACTIVITY_LED_DEV8-PadA)") (class "Default")
      (node (ref "ACTIVITY_LED_DEV8") (pin "A") (pinfunction "A_A") (pintype "passive"))
      (node (ref "R20") (pin "2") (pinfunction "2_2") (pintype "passive"))
    )
    (net (code "46") (name "Net-(ACTIVITY_LED_DEV9-PadA)") (class "Default")
      (node (ref "ACTIVITY_LED_DEV9") (pin "A") (pinfunction "A_A") (pintype "passive"))
      (node (ref "R21") (pin "2") (pinfunction "2_2") (pintype "passive"))
    )
    (net (code "47") (name "Net-(ACTIVITY_LED_DEV10-PadA)") (class "Default")
      (node (ref "ACTIVITY_LED_DEV10") (pin "A") (pinfunction "A_A") (pintype "passive"))
      (node (ref "R22") (pin "2") (pinfunction "2_2") (pintype "passive"))
    )
    (net (code "48") (name "Net-(BUT_RESET-S1)") (class "Default")
      (node (ref "BUT_RESET") (pin "2") (pinfunction "S1_2") (pintype "passive"))
      (node (ref "R3") (pin "2") (pinfunction "2_2") (pintype "passive"))
    )
    (net (code "49") (name "Net-(PWR_LED-PadA)") (class "Default")
      (node (ref "PWR_LED") (pin "A") (pinfunction "A_A") (pintype "passive"))
      (node (ref "R17") (pin "2") (pinfunction "2_2") (pintype "passive"))
    )
    (net (code "50") (name "Net-(Q2-B)") (class "Default")
      (node (ref "Q2") (pin "1") (pinfunction "B_1") (pintype "passive"))
      (node (ref "R7") (pin "1") (pinfunction "1_1") (pintype "passive"))
    )
    (net (code "51") (name "Net-(Q3-B)") (class "Default")
      (node (ref "Q3") (pin "1") (pinfunction "B_1") (pintype "passive"))
      (node (ref "R1") (pin "1") (pinfunction "1_1") (pintype "passive"))
    )
    (net (code "52") (name "Net-(U$1-RX)") (class "Default")
      (node (ref "R9") (pin "1") (pinfunction "1_1") (pintype "passive"))
      (node (ref "U$1") (pin "3") (pinfunction "RX_3") (pintype "bidirectional"))
    )
    (net (code "53") (name "Net-(U$1-TX)") (class "Default")
      (node (ref "R8") (pin "1") (pinfunction "1_1") (pintype "passive"))
      (node (ref "U$1") (pin "2") (pinfunction "TX_2") (pintype "bidirectional"))
    )
    (net (code "54") (name "Net-(U$1-XI)") (class "Default")
      (node (ref "C3") (pin "1") (pinfunction "1_1") (pintype "passive"))
      (node (ref "Q1") (pin "2") (pinfunction "2_2") (pintype "passive"))
      (node (ref "U$1") (pin "7") (pinfunction "XI_7") (pintype "bidirectional"))
    )
    (net (code "55") (name "Net-(U$1-XO)") (class "Default")
      (node (ref "C1") (pin "1") (pinfunction "1_1") (pintype "passive"))
      (node (ref "Q1") (pin "1") (pinfunction "1_1") (pintype "passive"))
      (node (ref "U$1") (pin "8") (pinfunction "XO_8") (pintype "bidirectional"))
    )
    (net (code "56") (name "PROG_BUT") (class "Default")
      (node (ref "BUT_PROG") (pin "2") (pinfunction "S1_2") (pintype "passive"))
      (node (ref "MDL1") (pin "10") (pinfunction "GPIO15_10") (pintype "bidirectional"))
      (node (ref "R12") (pin "2") (pinfunction "2_2") (pintype "passive"))
    )
    (net (code "57") (name "RESET_0") (class "Default")
      (node (ref "PROG_IN1") (pin "5") (pinfunction "5_5") (pintype "passive"))
      (node (ref "U2") (pin "8") (pinfunction "SIG_C_IN/OUT_8") (pintype "bidirectional"))
    )
    (net (code "58") (name "RESET_1") (class "Default")
      (node (ref "PROG_IN2") (pin "5") (pinfunction "5_5") (pintype "passive"))
      (node (ref "U1") (pin "8") (pinfunction "SIG_C_IN/OUT_8") (pintype "bidirectional"))
    )
    (net (code "59") (name "RESET_2") (class "Default")
      (node (ref "PROG_IN3") (pin "5") (pinfunction "5_5") (pintype "passive"))
      (node (ref "U3") (pin "8") (pinfunction "SIG_C_IN/OUT_8") (pintype "bidirectional"))
    )
    (net (code "60") (name "RESET_3") (class "Default")
      (node (ref "PROG_IN4") (pin "5") (pinfunction "5_5") (pintype "passive"))
      (node (ref "U4") (pin "8") (pinfunction "SIG_C_IN/OUT_8") (pintype "bidirectional"))
    )
    (net (code "61") (name "RESET_4") (class "Default")
      (node (ref "PROG_IN5") (pin "5") (pinfunction "5_5") (pintype "passive"))
      (node (ref "U5") (pin "8") (pinfunction "SIG_C_IN/OUT_8") (pintype "bidirectional"))
    )
    (net (code "62") (name "RESET_5") (class "Default")
      (node (ref "PROG_IN6") (pin "5") (pinfunction "5_5") (pintype "passive"))
      (node (ref "U6") (pin "8") (pinfunction "SIG_C_IN/OUT_8") (pintype "bidirectional"))
    )
    (net (code "63") (name "RESET_6") (class "Default")
      (node (ref "PROG_IN7") (pin "5") (pinfunction "5_5") (pintype "passive"))
      (node (ref "U7") (pin "8") (pinfunction "SIG_C_IN/OUT_8") (pintype "bidirectional"))
    )
    (net (code "64") (name "RESET_7") (class "Default")
      (node (ref "PROG_IN8") (pin "5") (pinfunction "5_5") (pintype "passive"))
      (node (ref "U8") (pin "8") (pinfunction "SIG_C_IN/OUT_8") (pintype "bidirectional"))
    )
    (net (code "65") (name "RESET_BUS") (class "Default")
      (node (ref "PROG_IN9") (pin "5") (pinfunction "5_5") (pintype "passive"))
      (node (ref "R29") (pin "2") (pinfunction "2_2") (pintype "passive"))
      (node (ref "U1") (pin "9") (pinfunction "SIG_C_OUT/IN_9") (pintype "bidirectional"))
      (node (ref "U2") (pin "9") (pinfunction "SIG_C_OUT/IN_9") (pintype "bidirectional"))
      (node (ref "U3") (pin "9") (pinfunction "SIG_C_OUT/IN_9") (pintype "bidirectional"))
      (node (ref "U4") (pin "9") (pinfunction "SIG_C_OUT/IN_9") (pintype "bidirectional"))
      (node (ref "U5") (pin "9") (pinfunction "SIG_C_OUT/IN_9") (pintype "bidirectional"))
      (node (ref "U6") (pin "9") (pinfunction "SIG_C_OUT/IN_9") (pintype "bidirectional"))
      (node (ref "U7") (pin "9") (pinfunction "SIG_C_OUT/IN_9") (pintype "bidirectional"))
      (node (ref "U8") (pin "9") (pinfunction "SIG_C_OUT/IN_9") (pintype "bidirectional"))
    )
    (net (code "66") (name "RESET_BUS_DIV") (class "Default")
      (node (ref "MDL1") (pin "14") (pinfunction "GPIO5_14") (pintype "bidirectional"))
      (node (ref "R29") (pin "1") (pinfunction "1_1") (pintype "passive"))
    )
    (net (code "67") (name "RESET_BUT") (class "Default")
      (node (ref "MDL1") (pin "2") (pinfunction "ADC_2") (pintype "bidirectional"))
      (node (ref "R3") (pin "1") (pinfunction "1_1") (pintype "passive"))
      (node (ref "R4") (pin "2") (pinfunction "2_2") (pintype "passive"))
    )
    (net (code "68") (name "RTS") (class "Default")
      (node (ref "Q3") (pin "2") (pinfunction "E_2") (pintype "passive"))
      (node (ref "R7") (pin "2") (pinfunction "2_2") (pintype "passive"))
      (node (ref "U$1") (pin "14") (pinfunction "RTS_14") (pintype "bidirectional"))
    )
    (net (code "69") (name "RX") (class "Default")
      (node (ref "MDL1") (pin "15") (pinfunction "RXD_15") (pintype "bidirectional"))
      (node (ref "R8") (pin "2") (pinfunction "2_2") (pintype "passive"))
    )
    (net (code "70") (name "SCK_0") (class "Default")
      (node (ref "PROG_IN1") (pin "3") (pinfunction "3_3") (pintype "passive"))
      (node (ref "U2") (pin "4") (pinfunction "SIG_B_IN/OUT_4") (pintype "bidirectional"))
    )
    (net (code "71") (name "SCK_1") (class "Default")
      (node (ref "PROG_IN2") (pin "3") (pinfunction "3_3") (pintype "passive"))
      (node (ref "U1") (pin "4") (pinfunction "SIG_B_IN/OUT_4") (pintype "bidirectional"))
    )
    (net (code "72") (name "SCK_2") (class "Default")
      (node (ref "PROG_IN3") (pin "3") (pinfunction "3_3") (pintype "passive"))
      (node (ref "U3") (pin "4") (pinfunction "SIG_B_IN/OUT_4") (pintype "bidirectional"))
    )
    (net (code "73") (name "SCK_3") (class "Default")
      (node (ref "PROG_IN4") (pin "3") (pinfunction "3_3") (pintype "passive"))
      (node (ref "U4") (pin "4") (pinfunction "SIG_B_IN/OUT_4") (pintype "bidirectional"))
    )
    (net (code "74") (name "SCK_4") (class "Default")
      (node (ref "PROG_IN5") (pin "3") (pinfunction "3_3") (pintype "passive"))
      (node (ref "U5") (pin "4") (pinfunction "SIG_B_IN/OUT_4") (pintype "bidirectional"))
    )
    (net (code "75") (name "SCK_5") (class "Default")
      (node (ref "PROG_IN6") (pin "3") (pinfunction "3_3") (pintype "passive"))
      (node (ref "U6") (pin "4") (pinfunction "SIG_B_IN/OUT_4") (pintype "bidirectional"))
    )
    (net (code "76") (name "SCK_6") (class "Default")
      (node (ref "PROG_IN7") (pin "3") (pinfunction "3_3") (pintype "passive"))
      (node (ref "U7") (pin "4") (pinfunction "SIG_B_IN/OUT_4") (pintype "bidirectional"))
    )
    (net (code "77") (name "SCK_7") (class "Default")
      (node (ref "PROG_IN8") (pin "3") (pinfunction "3_3") (pintype "passive"))
      (node (ref "U8") (pin "4") (pinfunction "SIG_B_IN/OUT_4") (pintype "bidirectional"))
    )
    (net (code "78") (name "SCK_BUS") (class "Default")
      (node (ref "PROG_IN9") (pin "3") (pinfunction "3_3") (pintype "passive"))
      (node (ref "R22") (pin "1") (pinfunction "1_1") (pintype "passive"))
      (node (ref "R23") (pin "2") (pinfunction "2_2") (pintype "passive"))
      (node (ref "U1") (pin "3") (pinfunction "SIG_B_OUT/IN_3") (pintype "bidirectional"))
      (node (ref "U2") (pin "3") (pinfunction "SIG_B_OUT/IN_3") (pintype "bidirectional"))
      (node (ref "U3") (pin "3") (pinfunction "SIG_B_OUT/IN_3") (pintype "bidirectional"))
      (node (ref "U4") (pin "3") (pinfunction "SIG_B_OUT/IN_3") (pintype "bidirectional"))
      (node (ref "U5") (pin "3") (pinfunction "SIG_B_OUT/IN_3") (pintype "bidirectional"))
      (node (ref "U6") (pin "3") (pinfunction "SIG_B_OUT/IN_3") (pintype "bidirectional"))
      (node (ref "U7") (pin "3") (pinfunction "SIG_B_OUT/IN_3") (pintype "bidirectional"))
      (node (ref "U8") (pin "3") (pinfunction "SIG_B_OUT/IN_3") (pintype "bidirectional"))
    )
    (net (code "79") (name "SCK_BUS_DIV") (class "Default")
      (node (ref "MDL1") (pin "5") (pinfunction "GPIO14_5") (pintype "bidirectional"))
      (node (ref "R23") (pin "1") (pinfunction "1_1") (pintype "passive"))
      (node (ref "R24") (pin "2") (pinfunction "2_2") (pintype "passive"))
    )
    (net (code "80") (name "SHCP") (class "Default")
      (node (ref "IC1") (pin "11") (pinfunction "SCK_11") (pintype "input"))
      (node (ref "MDL1") (pin "12") (pinfunction "GPIO0_12") (pintype "bidirectional"))
      (node (ref "Q2") (pin "3") (pinfunction "C_3") (pintype "passive"))
      (node (ref "R10") (pin "1") (pinfunction "1_1") (pintype "passive"))
    )
    (net (code "81") (name "STCP") (class "Default")
      (node (ref "IC1") (pin "12") (pinfunction "RCK_12") (pintype "input"))
      (node (ref "MDL1") (pin "13") (pinfunction "GPIO4_13") (pintype "bidirectional"))
    )
    (net (code "82") (name "SUPPLY") (class "Default")
      (node (ref "3V3_REGULATOR") (pin "1") (pinfunction "IN_1") (pintype "power_in"))
      (node (ref "3V3_REGULATOR") (pin "3") (pinfunction "EN_3") (pintype "input"))
      (node (ref "C8") (pin "+") (pinfunction "+_+") (pintype "passive"))
      (node (ref "J2") (pin "1") (pinfunction "VUSB_1") (pintype "passive"))
      (node (ref "SW1") (pin "3") (pinfunction "O_3") (pintype "passive"))
    )
    (net (code "83") (name "TX") (class "Default")
      (node (ref "MDL1") (pin "16") (pinfunction "TXD_16") (pintype "bidirectional"))
      (node (ref "R9") (pin "2") (pinfunction "2_2") (pintype "passive"))
    )
    (net (code "84") (name "VCC") (class "Default")
      (node (ref "3V3_REGULATOR") (pin "5") (pinfunction "OUT_5") (pintype "power_in"))
      (node (ref "BUT_PROG") (pin "4") (pinfunction "P1_4") (pintype "passive"))
      (node (ref "BUT_RESET") (pin "4") (pinfunction "P1_4") (pintype "passive"))
      (node (ref "C11") (pin "+") (pinfunction "+_+") (pintype "passive"))
      (node (ref "C2") (pin "1") (pinfunction "1_1") (pintype "passive"))
      (node (ref "C4") (pin "1") (pinfunction "1_1") (pintype "passive"))
      (node (ref "C6") (pin "2") (pinfunction "2_2") (pintype "passive"))
      (node (ref "C7") (pin "2") (pinfunction "2_2") (pintype "passive"))
      (node (ref "MDL1") (pin "3") (pinfunction "CH_PD_3") (pintype "bidirectional"))
      (node (ref "MDL1") (pin "8") (pinfunction "VCC_8") (pintype "bidirectional"))
      (node (ref "R10") (pin "2") (pinfunction "2_2") (pintype "passive"))
      (node (ref "R11") (pin "2") (pinfunction "2_2") (pintype "passive"))
      (node (ref "R17") (pin "1") (pinfunction "1_1") (pintype "passive"))
      (node (ref "R2") (pin "2") (pinfunction "2_2") (pintype "passive"))
      (node (ref "SW1") (pin "1") (pinfunction "S_1") (pintype "passive"))
      (node (ref "U$1") (pin "16") (pinfunction "VCC_16") (pintype "bidirectional"))
      (node (ref "U$1") (pin "4") (pinfunction "V3_4") (pintype "bidirectional"))
      (node (ref "U1") (pin "14") (pinfunction "VDD_14") (pintype "power_in"))
      (node (ref "U2") (pin "14") (pinfunction "VDD_14") (pintype "power_in"))
      (node (ref "U3") (pin "14") (pinfunction "VDD_14") (pintype "power_in"))
      (node (ref "U4") (pin "14") (pinfunction "VDD_14") (pintype "power_in"))
      (node (ref "U5") (pin "14") (pinfunction "VDD_14") (pintype "power_in"))
      (node (ref "U6") (pin "14") (pinfunction "VDD_14") (pintype "power_in"))
      (node (ref "U7") (pin "14") (pinfunction "VDD_14") (pintype "power_in"))
      (node (ref "U8") (pin "14") (pinfunction "VDD_14") (pintype "power_in"))
    )
    (net (code "85") (name "unconnected-(3V3_REGULATOR-NC-Pad4)") (class "Default")
      (node (ref "3V3_REGULATOR") (pin "4") (pinfunction "NC_4") (pintype "no_connect"))
    )
    (net (code "86") (name "unconnected-(BUT_PROG-P-Pad3)") (class "Default")
      (node (ref "BUT_PROG") (pin "3") (pinfunction "P_3") (pintype "passive"))
    )
    (net (code "87") (name "unconnected-(BUT_PROG-S-Pad1)") (class "Default")
      (node (ref "BUT_PROG") (pin "1") (pinfunction "S_1") (pintype "passive"))
    )
    (net (code "88") (name "unconnected-(BUT_RESET-P-Pad3)") (class "Default")
      (node (ref "BUT_RESET") (pin "3") (pinfunction "P_3") (pintype "passive"))
    )
    (net (code "89") (name "unconnected-(BUT_RESET-S-Pad1)") (class "Default")
      (node (ref "BUT_RESET") (pin "1") (pinfunction "S_1") (pintype "passive"))
    )
    (net (code "90") (name "unconnected-(IC1A-QH*-Pad9)") (class "Default")
      (node (ref "IC1") (pin "9") (pinfunction "QH*_9") (pintype "tri_state"))
    )
    (net (code "91") (name "unconnected-(J2-ID-Pad4)") (class "Default")
      (node (ref "J2") (pin "4") (pinfunction "ID_4") (pintype "passive"))
    )
    (net (code "92") (name "unconnected-(U$1-CTS-Pad9)") (class "Default")
      (node (ref "U$1") (pin "9") (pinfunction "CTS_9") (pintype "bidirectional"))
    )
    (net (code "93") (name "unconnected-(U$1-DCD-Pad12)") (class "Default")
      (node (ref "U$1") (pin "12") (pinfunction "DCD_12") (pintype "bidirectional"))
    )
    (net (code "94") (name "unconnected-(U$1-DSR-Pad10)") (class "Default")
      (node (ref "U$1") (pin "10") (pinfunction "DSR_10") (pintype "bidirectional"))
    )
    (net (code "95") (name "unconnected-(U$1-RI-Pad11)") (class "Default")
      (node (ref "U$1") (pin "11") (pinfunction "RI_11") (pintype "bidirectional"))
    )
    (net (code "96") (name "unconnected-(U$1-RS232-Pad15)") (class "Default")
      (node (ref "U$1") (pin "15") (pinfunction "RS232_15") (pintype "bidirectional"))
    )
  )
)
